# Sht3-V12P0_reg.net
KiCad netlist of a schematic drawn in Altium Designer
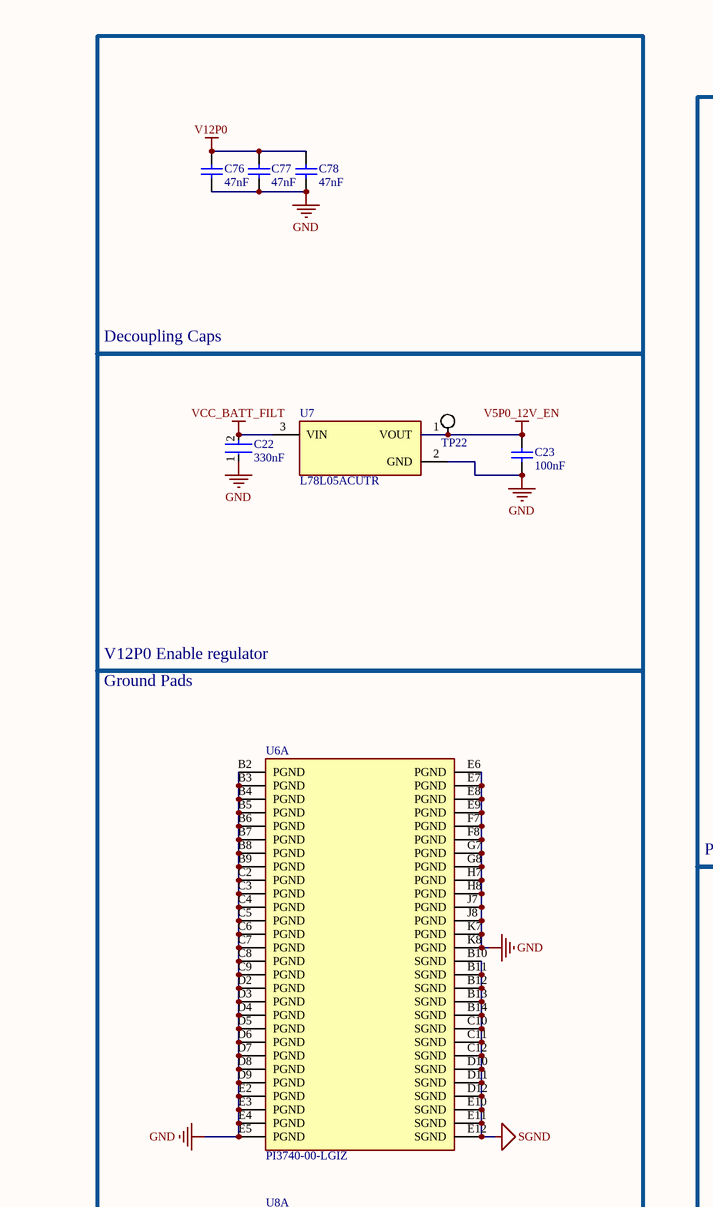
[diagram p0: Sht3-V12P0_reg.SchDoc, top left]
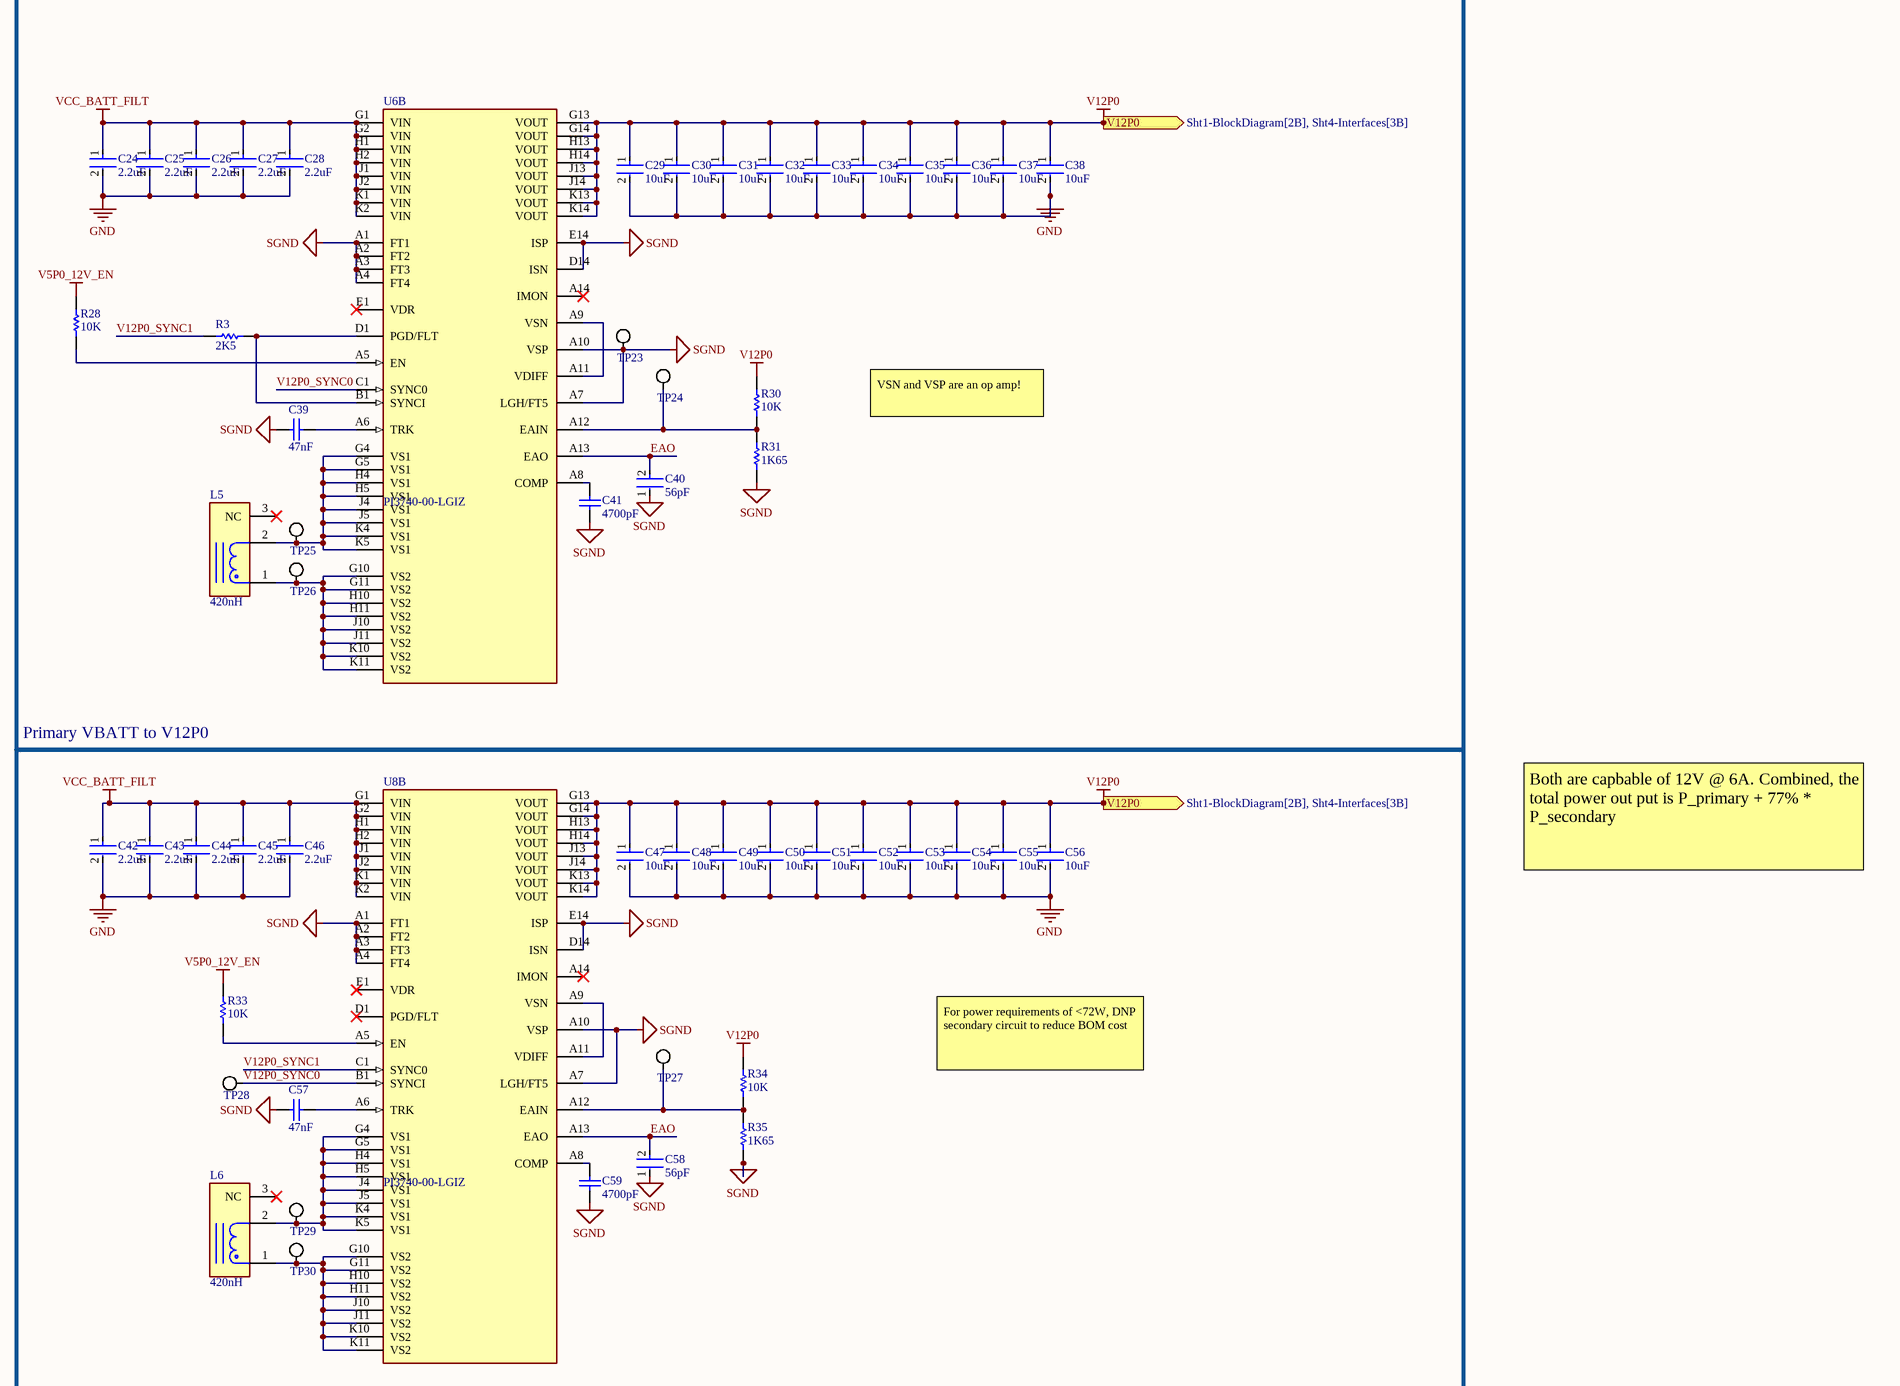
[diagram p1: Sht3-V12P0_reg.SchDoc, top right]
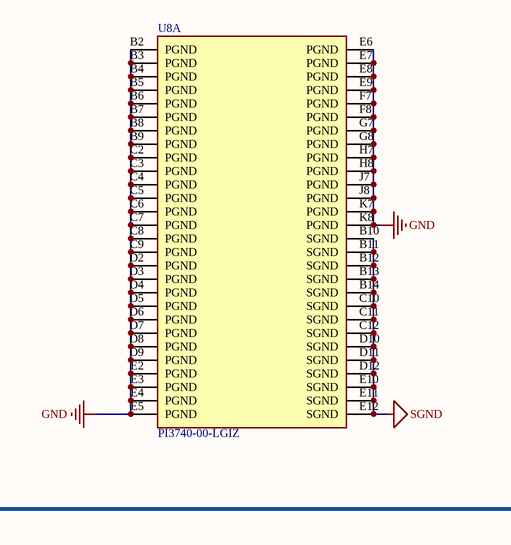
[diagram p2: Sht3-V12P0_reg.SchDoc, bottom left]
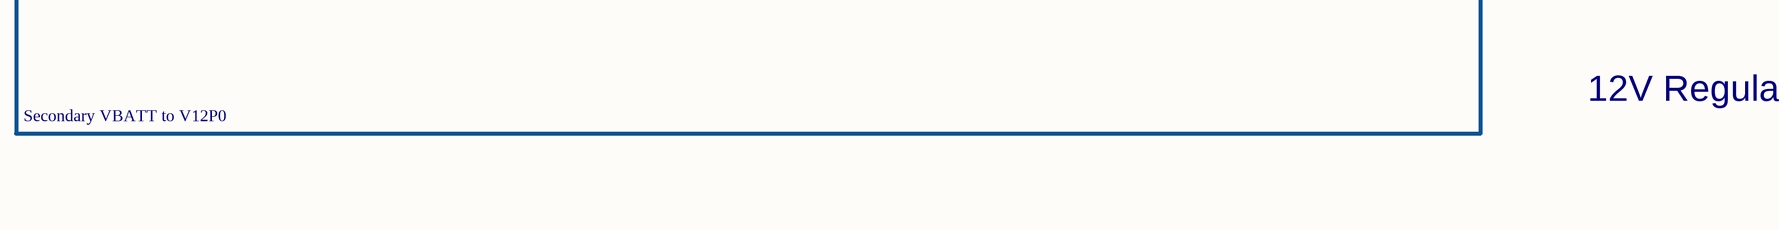
[diagram p3: Sht3-V12P0_reg.SchDoc, bottom right]

(export (version "E")
  (design (tool "Eeschema 10.0.6"))
  (components
    (comp (ref "C22")
      (value "330nF")
      (footprint "FP-C1608-080-0_1-IPC_A")
      (description "Multilayer Ceramic Capacitors 330nF ±10% 50V X7R SMD 0603")
      (fields (field (name "TOLERANCE") "10%") (field (name "VOLTAGE") "50V"))
      (libsource (lib "TAUV-Lib") (part "330nF 0603"))
    )
    (comp (ref "C23")
      (value "100nF")
      (footprint "CAPC0603(1608)100_L")
      (description "CAP 100nF 100V ±10% 0603 (1608 Metric) Thickness 1mm SMD")
      (fields (field (name "TOLERANCE") "Â±10%"))
      (libsource (lib "TAUV-Lib") (part "100nF 0603"))
    )
    (comp (ref "C24")
      (value "2.2uF")
      (footprint "FP-1210-L_3_3_0_4-W_2_5_0-IPC_B")
      (description "General Purpose Ceramic Capacitor, 1210, 2.2uF, 10%, X7R, 15%, 100V")
      (fields (field (name "TOLERANCE") "10%") (field (name "VOLTAGE") "100V"))
      (libsource (lib "TAUV-Lib") (part "2.2uF 1210"))
    )
    (comp (ref "C25")
      (value "2.2uF")
      (footprint "FP-1210-L_3_3_0_4-W_2_5_0-IPC_B")
      (description "General Purpose Ceramic Capacitor, 1210, 2.2uF, 10%, X7R, 15%, 100V")
      (fields (field (name "TOLERANCE") "10%") (field (name "VOLTAGE") "100V"))
      (libsource (lib "TAUV-Lib") (part "2.2uF 1210"))
    )
    (comp (ref "C26")
      (value "2.2uF")
      (footprint "FP-1210-L_3_3_0_4-W_2_5_0-IPC_B")
      (description "General Purpose Ceramic Capacitor, 1210, 2.2uF, 10%, X7R, 15%, 100V")
      (fields (field (name "TOLERANCE") "10%") (field (name "VOLTAGE") "100V"))
      (libsource (lib "TAUV-Lib") (part "2.2uF 1210"))
    )
    (comp (ref "C27")
      (value "2.2uF")
      (footprint "FP-1210-L_3_3_0_4-W_2_5_0-IPC_B")
      (description "General Purpose Ceramic Capacitor, 1210, 2.2uF, 10%, X7R, 15%, 100V")
      (fields (field (name "TOLERANCE") "10%") (field (name "VOLTAGE") "100V"))
      (libsource (lib "TAUV-Lib") (part "2.2uF 1210"))
    )
    (comp (ref "C28")
      (value "2.2uF")
      (footprint "FP-1210-L_3_3_0_4-W_2_5_0-IPC_B")
      (description "General Purpose Ceramic Capacitor, 1210, 2.2uF, 10%, X7R, 15%, 100V")
      (fields (field (name "TOLERANCE") "10%") (field (name "VOLTAGE") "100V"))
      (libsource (lib "TAUV-Lib") (part "2.2uF 1210"))
    )
    (comp (ref "C29")
      (value "10uF")
      (footprint "FP-GRM32-MFG")
      (description "CAP CER 10UF 50V X7R 1210")
      (fields (field (name "TOLERANCE") "10%") (field (name "MANUFACTURER PART NUMBER") "GRM32ER71H106KA12L"))
      (libsource (lib "TAUV-Lib") (part "10uF 1210"))
    )
    (comp (ref "C30")
      (value "10uF")
      (footprint "FP-GRM32-MFG")
      (description "CAP CER 10UF 50V X7R 1210")
      (fields (field (name "TOLERANCE") "10%") (field (name "MANUFACTURER PART NUMBER") "GRM32ER71H106KA12L"))
      (libsource (lib "TAUV-Lib") (part "10uF 1210"))
    )
    (comp (ref "C31")
      (value "10uF")
      (footprint "FP-GRM32-MFG")
      (description "CAP CER 10UF 50V X7R 1210")
      (fields (field (name "TOLERANCE") "10%") (field (name "MANUFACTURER PART NUMBER") "GRM32ER71H106KA12L"))
      (libsource (lib "TAUV-Lib") (part "10uF 1210"))
    )
    (comp (ref "C32")
      (value "10uF")
      (footprint "FP-GRM32-MFG")
      (description "CAP CER 10UF 50V X7R 1210")
      (fields (field (name "TOLERANCE") "10%") (field (name "MANUFACTURER PART NUMBER") "GRM32ER71H106KA12L"))
      (libsource (lib "TAUV-Lib") (part "10uF 1210"))
    )
    (comp (ref "C33")
      (value "10uF")
      (footprint "FP-GRM32-MFG")
      (description "CAP CER 10UF 50V X7R 1210")
      (fields (field (name "TOLERANCE") "10%") (field (name "MANUFACTURER PART NUMBER") "GRM32ER71H106KA12L"))
      (libsource (lib "TAUV-Lib") (part "10uF 1210"))
    )
    (comp (ref "C34")
      (value "10uF")
      (footprint "FP-GRM32-MFG")
      (description "CAP CER 10UF 50V X7R 1210")
      (fields (field (name "TOLERANCE") "10%") (field (name "MANUFACTURER PART NUMBER") "GRM32ER71H106KA12L"))
      (libsource (lib "TAUV-Lib") (part "10uF 1210"))
    )
    (comp (ref "C35")
      (value "10uF")
      (footprint "FP-GRM32-MFG")
      (description "CAP CER 10UF 50V X7R 1210")
      (fields (field (name "TOLERANCE") "10%") (field (name "MANUFACTURER PART NUMBER") "GRM32ER71H106KA12L"))
      (libsource (lib "TAUV-Lib") (part "10uF 1210"))
    )
    (comp (ref "C36")
      (value "10uF")
      (footprint "FP-GRM32-MFG")
      (description "CAP CER 10UF 50V X7R 1210")
      (fields (field (name "TOLERANCE") "10%") (field (name "MANUFACTURER PART NUMBER") "GRM32ER71H106KA12L"))
      (libsource (lib "TAUV-Lib") (part "10uF 1210"))
    )
    (comp (ref "C37")
      (value "10uF")
      (footprint "FP-GRM32-MFG")
      (description "CAP CER 10UF 50V X7R 1210")
      (fields (field (name "TOLERANCE") "10%") (field (name "MANUFACTURER PART NUMBER") "GRM32ER71H106KA12L"))
      (libsource (lib "TAUV-Lib") (part "10uF 1210"))
    )
    (comp (ref "C38")
      (value "10uF")
      (footprint "FP-GRM32-MFG")
      (description "CAP CER 10UF 50V X7R 1210")
      (fields (field (name "TOLERANCE") "10%") (field (name "MANUFACTURER PART NUMBER") "GRM32ER71H106KA12L"))
      (libsource (lib "TAUV-Lib") (part "10uF 1210"))
    )
    (comp (ref "C39")
      (value "47nF")
      (footprint "CAPC1608X90X35LL10T15")
      (description "47nF 0603")
      (fields (field (name "MANUFACTURER") "Murata") (field (name "PART NUMBER") "GRM188R71E473KA01D"))
      (libsource (lib "TAUV-Lib") (part "47nF 0603"))
    )
    (comp (ref "C40")
      (value "56pF")
      (footprint "FP-C1608-080-0_1-IPC_C")
      (description "Multilayer Ceramic Capacitors 56pF ±5% 50V C0G SMD 0603")
      (fields (field (name "TOLERANCE") "5%"))
      (libsource (lib "TAUV-Lib") (part "56pF 0603"))
    )
    (comp (ref "C41")
      (value "4700pF")
      (footprint "CAPC1608X90X35ML10T15")
      (description "4700pF 0603")
      (fields (field (name "PART NUMBER") "GRM188R72A472KA01D") (field (name "MANUFACTURER") "Murata"))
      (libsource (lib "TAUV-Lib") (part "4700pF 0603"))
    )
    (comp (ref "C42")
      (value "2.2uF")
      (footprint "FP-1210-L_3_3_0_4-W_2_5_0-IPC_B")
      (description "General Purpose Ceramic Capacitor, 1210, 2.2uF, 10%, X7R, 15%, 100V")
      (fields (field (name "TOLERANCE") "10%") (field (name "VOLTAGE") "100V"))
      (libsource (lib "TAUV-Lib") (part "2.2uF 1210"))
    )
    (comp (ref "C43")
      (value "2.2uF")
      (footprint "FP-1210-L_3_3_0_4-W_2_5_0-IPC_B")
      (description "General Purpose Ceramic Capacitor, 1210, 2.2uF, 10%, X7R, 15%, 100V")
      (fields (field (name "TOLERANCE") "10%") (field (name "VOLTAGE") "100V"))
      (libsource (lib "TAUV-Lib") (part "2.2uF 1210"))
    )
    (comp (ref "C44")
      (value "2.2uF")
      (footprint "FP-1210-L_3_3_0_4-W_2_5_0-IPC_B")
      (description "General Purpose Ceramic Capacitor, 1210, 2.2uF, 10%, X7R, 15%, 100V")
      (fields (field (name "TOLERANCE") "10%") (field (name "VOLTAGE") "100V"))
      (libsource (lib "TAUV-Lib") (part "2.2uF 1210"))
    )
    (comp (ref "C45")
      (value "2.2uF")
      (footprint "FP-1210-L_3_3_0_4-W_2_5_0-IPC_B")
      (description "General Purpose Ceramic Capacitor, 1210, 2.2uF, 10%, X7R, 15%, 100V")
      (fields (field (name "TOLERANCE") "10%") (field (name "VOLTAGE") "100V"))
      (libsource (lib "TAUV-Lib") (part "2.2uF 1210"))
    )
    (comp (ref "C46")
      (value "2.2uF")
      (footprint "FP-1210-L_3_3_0_4-W_2_5_0-IPC_B")
      (description "General Purpose Ceramic Capacitor, 1210, 2.2uF, 10%, X7R, 15%, 100V")
      (fields (field (name "TOLERANCE") "10%") (field (name "VOLTAGE") "100V"))
      (libsource (lib "TAUV-Lib") (part "2.2uF 1210"))
    )
    (comp (ref "C47")
      (value "10uF")
      (footprint "FP-GRM32-MFG")
      (description "CAP CER 10UF 50V X7R 1210")
      (fields (field (name "TOLERANCE") "10%") (field (name "MANUFACTURER PART NUMBER") "GRM32ER71H106KA12L"))
      (libsource (lib "TAUV-Lib") (part "10uF 1210"))
    )
    (comp (ref "C48")
      (value "10uF")
      (footprint "FP-GRM32-MFG")
      (description "CAP CER 10UF 50V X7R 1210")
      (fields (field (name "TOLERANCE") "10%") (field (name "MANUFACTURER PART NUMBER") "GRM32ER71H106KA12L"))
      (libsource (lib "TAUV-Lib") (part "10uF 1210"))
    )
    (comp (ref "C49")
      (value "10uF")
      (footprint "FP-GRM32-MFG")
      (description "CAP CER 10UF 50V X7R 1210")
      (fields (field (name "TOLERANCE") "10%") (field (name "MANUFACTURER PART NUMBER") "GRM32ER71H106KA12L"))
      (libsource (lib "TAUV-Lib") (part "10uF 1210"))
    )
    (comp (ref "C50")
      (value "10uF")
      (footprint "FP-GRM32-MFG")
      (description "CAP CER 10UF 50V X7R 1210")
      (fields (field (name "TOLERANCE") "10%") (field (name "MANUFACTURER PART NUMBER") "GRM32ER71H106KA12L"))
      (libsource (lib "TAUV-Lib") (part "10uF 1210"))
    )
    (comp (ref "C51")
      (value "10uF")
      (footprint "FP-GRM32-MFG")
      (description "CAP CER 10UF 50V X7R 1210")
      (fields (field (name "TOLERANCE") "10%") (field (name "MANUFACTURER PART NUMBER") "GRM32ER71H106KA12L"))
      (libsource (lib "TAUV-Lib") (part "10uF 1210"))
    )
    (comp (ref "C52")
      (value "10uF")
      (footprint "FP-GRM32-MFG")
      (description "CAP CER 10UF 50V X7R 1210")
      (fields (field (name "TOLERANCE") "10%") (field (name "MANUFACTURER PART NUMBER") "GRM32ER71H106KA12L"))
      (libsource (lib "TAUV-Lib") (part "10uF 1210"))
    )
    (comp (ref "C53")
      (value "10uF")
      (footprint "FP-GRM32-MFG")
      (description "CAP CER 10UF 50V X7R 1210")
      (fields (field (name "TOLERANCE") "10%") (field (name "MANUFACTURER PART NUMBER") "GRM32ER71H106KA12L"))
      (libsource (lib "TAUV-Lib") (part "10uF 1210"))
    )
    (comp (ref "C54")
      (value "10uF")
      (footprint "FP-GRM32-MFG")
      (description "CAP CER 10UF 50V X7R 1210")
      (fields (field (name "TOLERANCE") "10%") (field (name "MANUFACTURER PART NUMBER") "GRM32ER71H106KA12L"))
      (libsource (lib "TAUV-Lib") (part "10uF 1210"))
    )
    (comp (ref "C55")
      (value "10uF")
      (footprint "FP-GRM32-MFG")
      (description "CAP CER 10UF 50V X7R 1210")
      (fields (field (name "TOLERANCE") "10%") (field (name "MANUFACTURER PART NUMBER") "GRM32ER71H106KA12L"))
      (libsource (lib "TAUV-Lib") (part "10uF 1210"))
    )
    (comp (ref "C56")
      (value "10uF")
      (footprint "FP-GRM32-MFG")
      (description "CAP CER 10UF 50V X7R 1210")
      (fields (field (name "TOLERANCE") "10%") (field (name "MANUFACTURER PART NUMBER") "GRM32ER71H106KA12L"))
      (libsource (lib "TAUV-Lib") (part "10uF 1210"))
    )
    (comp (ref "C57")
      (value "47nF")
      (footprint "CAPC1608X90X35LL10T15")
      (description "47nF 0603")
      (fields (field (name "MANUFACTURER") "Murata") (field (name "PART NUMBER") "GRM188R71E473KA01D"))
      (libsource (lib "TAUV-Lib") (part "47nF 0603"))
    )
    (comp (ref "C58")
      (value "56pF")
      (footprint "FP-C1608-080-0_1-IPC_C")
      (description "Multilayer Ceramic Capacitors 56pF ±5% 50V C0G SMD 0603")
      (fields (field (name "TOLERANCE") "5%"))
      (libsource (lib "TAUV-Lib") (part "56pF 0603"))
    )
    (comp (ref "C59")
      (value "4700pF")
      (footprint "CAPC1608X90X35ML10T15")
      (description "4700pF 0603")
      (fields (field (name "PART NUMBER") "GRM188R72A472KA01D") (field (name "MANUFACTURER") "Murata"))
      (libsource (lib "TAUV-Lib") (part "4700pF 0603"))
    )
    (comp (ref "C76")
      (value "47nF")
      (footprint "CAPC1608X90X35LL10T15")
      (description "47nF 0603")
      (fields (field (name "MANUFACTURER") "Murata") (field (name "PART NUMBER") "GRM188R71E473KA01D"))
      (libsource (lib "TAUV-Lib") (part "47nF 0603"))
    )
    (comp (ref "C77")
      (value "47nF")
      (footprint "CAPC1608X90X35LL10T15")
      (description "47nF 0603")
      (fields (field (name "MANUFACTURER") "Murata") (field (name "PART NUMBER") "GRM188R71E473KA01D"))
      (libsource (lib "TAUV-Lib") (part "47nF 0603"))
    )
    (comp (ref "C78")
      (value "47nF")
      (footprint "CAPC1608X90X35LL10T15")
      (description "47nF 0603")
      (fields (field (name "MANUFACTURER") "Murata") (field (name "PART NUMBER") "GRM188R71E473KA01D"))
      (libsource (lib "TAUV-Lib") (part "47nF 0603"))
    )
    (comp (ref "L5")
      (value "420nH")
      (footprint "FP-HCV1206-R42-R-MFG")
      (description "HCV1206-R42-R -FIXED IND 420NH 16A 3.15 MOHM")
      (fields (field (name "TOLERANCE") "10%"))
      (libsource (lib "TAUV-Lib") (part "HCV1206-R42-R"))
    )
    (comp (ref "L6")
      (value "420nH")
      (footprint "FP-HCV1206-R42-R-MFG")
      (description "HCV1206-R42-R -FIXED IND 420NH 16A 3.15 MOHM")
      (fields (field (name "TOLERANCE") "10%"))
      (libsource (lib "TAUV-Lib") (part "HCV1206-R42-R"))
    )
    (comp (ref "R3")
      (value "2K5")
      (footprint "RESC1608X55X25NL10T15")
      (description "2.5K 0603")
      (fields (field (name "MANUFACTURER") "Yageo") (field (name "PART NUMBER") "RC0603FR-072K55L"))
      (libsource (lib "TAUV-Lib") (part "2K5 0603"))
    )
    (comp (ref "R28")
      (value "10K")
      (footprint "RESC1609X50X30NL8T20")
      (description "Chip Resistor, 10 KOhm, +/- 1%, 100 mW, -55 to 155 degC, 0603 (1608 Metric), RoHS, Tape and Reel")
      (fields (field (name "MANUFACTURER") "Vishay Semiconductor"))
      (libsource (lib "TAUV-Lib") (part "10K 0603"))
    )
    (comp (ref "R30")
      (value "10K")
      (footprint "RESC1609X50X30NL8T20")
      (description "Chip Resistor, 10 KOhm, +/- 1%, 100 mW, -55 to 155 degC, 0603 (1608 Metric), RoHS, Tape and Reel")
      (fields (field (name "MANUFACTURER") "Vishay Semiconductor"))
      (libsource (lib "TAUV-Lib") (part "10K 0603"))
    )
    (comp (ref "R31")
      (value "1K65")
      (footprint "RESC1608X55X25ML10T15")
      (description "1.65k 0603")
      (fields (field (name "PART NUMBER") "RC0603FR-071K65L") (field (name "MANUFACTURER") "Yageo"))
      (libsource (lib "TAUV-Lib") (part "1K65 0603"))
    )
    (comp (ref "R33")
      (value "10K")
      (footprint "RESC1609X50X30NL8T20")
      (description "Chip Resistor, 10 KOhm, +/- 1%, 100 mW, -55 to 155 degC, 0603 (1608 Metric), RoHS, Tape and Reel")
      (fields (field (name "MANUFACTURER") "Vishay Semiconductor"))
      (libsource (lib "TAUV-Lib") (part "10K 0603"))
    )
    (comp (ref "R34")
      (value "10K")
      (footprint "RESC1609X50X30NL8T20")
      (description "Chip Resistor, 10 KOhm, +/- 1%, 100 mW, -55 to 155 degC, 0603 (1608 Metric), RoHS, Tape and Reel")
      (fields (field (name "MANUFACTURER") "Vishay Semiconductor"))
      (libsource (lib "TAUV-Lib") (part "10K 0603"))
    )
    (comp (ref "R35")
      (value "1K65")
      (footprint "RESC1608X55X25ML10T15")
      (description "1.65k 0603")
      (fields (field (name "PART NUMBER") "RC0603FR-071K65L") (field (name "MANUFACTURER") "Yageo"))
      (libsource (lib "TAUV-Lib") (part "1K65 0603"))
    )
    (comp (ref "TP22")
      (value "~")
      (footprint "Test Point Pad")
      (description "Test point, Pad, 28 mil")
      (libsource (lib "TAUV-Lib") (part "Test Point Pad"))
    )
    (comp (ref "TP23")
      (value "~")
      (footprint "Test Point Pad")
      (description "Test point, Pad, 28 mil")
      (libsource (lib "TAUV-Lib") (part "Test Point Pad"))
    )
    (comp (ref "TP24")
      (value "~")
      (footprint "Test Point Pad")
      (description "Test point, Pad, 28 mil")
      (libsource (lib "TAUV-Lib") (part "Test Point Pad"))
    )
    (comp (ref "TP25")
      (value "~")
      (footprint "Test Point Pad")
      (description "Test point, Pad, 28 mil")
      (libsource (lib "TAUV-Lib") (part "Test Point Pad"))
    )
    (comp (ref "TP26")
      (value "~")
      (footprint "Test Point Pad")
      (description "Test point, Pad, 28 mil")
      (libsource (lib "TAUV-Lib") (part "Test Point Pad"))
    )
    (comp (ref "TP27")
      (value "~")
      (footprint "Test Point Pad")
      (description "Test point, Pad, 28 mil")
      (libsource (lib "TAUV-Lib") (part "Test Point Pad"))
    )
    (comp (ref "TP28")
      (value "~")
      (footprint "Test Point Pad")
      (description "Test point, Pad, 28 mil")
      (libsource (lib "TAUV-Lib") (part "Test Point Pad"))
    )
    (comp (ref "TP29")
      (value "~")
      (footprint "Test Point Pad")
      (description "Test point, Pad, 28 mil")
      (libsource (lib "TAUV-Lib") (part "Test Point Pad"))
    )
    (comp (ref "TP30")
      (value "~")
      (footprint "Test Point Pad")
      (description "Test point, Pad, 28 mil")
      (libsource (lib "TAUV-Lib") (part "Test Point Pad"))
    )
    (comp (ref "U6")
      (value "PI3740-00-LGIZ")
      (footprint "FP-PI3740-00-LGIZ-MFG")
      (description "DC DC CONVERTER 10-50V")
      (libsource (lib "TAUV-Lib") (part "PI3740-00-LGIZ"))
    )
    (comp (ref "U7")
      (value "L78L05ACUTR")
      (footprint "FP-SOT-89-7098166-MFG")
      (description "IC REG LINEAR 5V 100MA SOT89-3")
      (libsource (lib "TAUV-Lib") (part "L78L05ACUTR"))
    )
    (comp (ref "U8")
      (value "PI3740-00-LGIZ")
      (footprint "FP-PI3740-00-LGIZ-MFG")
      (description "DC DC CONVERTER 10-50V")
      (libsource (lib "TAUV-Lib") (part "PI3740-00-LGIZ"))
    )
  )
  (nets
    (net (code "1") (name "/EAO") (class "Default")
      (node (ref "C40") (pin "2") (pinfunction "2_2") (pintype "passive"))
      (node (ref "C58") (pin "2") (pinfunction "2_2") (pintype "passive"))
      (node (ref "U6") (pin "A13") (pinfunction "EAO_A13") (pintype "passive"))
      (node (ref "U8") (pin "A13") (pinfunction "EAO_A13") (pintype "passive"))
    )
    (net (code "2") (name "/V12P0_SYNC0") (class "Default")
      (node (ref "TP28") (pin "1") (pinfunction "1_1") (pintype "passive"))
      (node (ref "U6") (pin "C1") (pinfunction "SYNC0_C1") (pintype "input"))
      (node (ref "U8") (pin "B1") (pinfunction "SYNCI_B1") (pintype "input"))
    )
    (net (code "3") (name "/V12P0_SYNC1") (class "Default")
      (node (ref "R3") (pin "1") (pinfunction "1_1") (pintype "passive"))
      (node (ref "U8") (pin "C1") (pinfunction "SYNC0_C1") (pintype "input"))
    )
    (net (code "4") (name "GND") (class "Default")
      (node (ref "C22") (pin "1") (pinfunction "1_1") (pintype "passive"))
      (node (ref "C23") (pin "2") (pinfunction "2_2") (pintype "passive"))
      (node (ref "C24") (pin "2") (pinfunction "2_2") (pintype "passive"))
      (node (ref "C25") (pin "2") (pinfunction "2_2") (pintype "passive"))
      (node (ref "C26") (pin "2") (pinfunction "2_2") (pintype "passive"))
      (node (ref "C27") (pin "2") (pinfunction "2_2") (pintype "passive"))
      (node (ref "C28") (pin "2") (pinfunction "2_2") (pintype "passive"))
      (node (ref "C29") (pin "2") (pinfunction "2_2") (pintype "passive"))
      (node (ref "C30") (pin "2") (pinfunction "2_2") (pintype "passive"))
      (node (ref "C31") (pin "2") (pinfunction "2_2") (pintype "passive"))
      (node (ref "C32") (pin "2") (pinfunction "2_2") (pintype "passive"))
      (node (ref "C33") (pin "2") (pinfunction "2_2") (pintype "passive"))
      (node (ref "C34") (pin "2") (pinfunction "2_2") (pintype "passive"))
      (node (ref "C35") (pin "2") (pinfunction "2_2") (pintype "passive"))
      (node (ref "C36") (pin "2") (pinfunction "2_2") (pintype "passive"))
      (node (ref "C37") (pin "2") (pinfunction "2_2") (pintype "passive"))
      (node (ref "C38") (pin "2") (pinfunction "2_2") (pintype "passive"))
      (node (ref "C42") (pin "2") (pinfunction "2_2") (pintype "passive"))
      (node (ref "C43") (pin "2") (pinfunction "2_2") (pintype "passive"))
      (node (ref "C44") (pin "2") (pinfunction "2_2") (pintype "passive"))
      (node (ref "C45") (pin "2") (pinfunction "2_2") (pintype "passive"))
      (node (ref "C46") (pin "2") (pinfunction "2_2") (pintype "passive"))
      (node (ref "C47") (pin "2") (pinfunction "2_2") (pintype "passive"))
      (node (ref "C48") (pin "2") (pinfunction "2_2") (pintype "passive"))
      (node (ref "C49") (pin "2") (pinfunction "2_2") (pintype "passive"))
      (node (ref "C50") (pin "2") (pinfunction "2_2") (pintype "passive"))
      (node (ref "C51") (pin "2") (pinfunction "2_2") (pintype "passive"))
      (node (ref "C52") (pin "2") (pinfunction "2_2") (pintype "passive"))
      (node (ref "C53") (pin "2") (pinfunction "2_2") (pintype "passive"))
      (node (ref "C54") (pin "2") (pinfunction "2_2") (pintype "passive"))
      (node (ref "C55") (pin "2") (pinfunction "2_2") (pintype "passive"))
      (node (ref "C56") (pin "2") (pinfunction "2_2") (pintype "passive"))
      (node (ref "C76") (pin "2") (pinfunction "2_2") (pintype "passive"))
      (node (ref "C77") (pin "2") (pinfunction "2_2") (pintype "passive"))
      (node (ref "C78") (pin "2") (pinfunction "2_2") (pintype "passive"))
      (node (ref "U6") (pin "B2") (pinfunction "PGND_B2") (pintype "power_in"))
      (node (ref "U6") (pin "B3") (pinfunction "PGND_B3") (pintype "power_in"))
      (node (ref "U6") (pin "B4") (pinfunction "PGND_B4") (pintype "power_in"))
      (node (ref "U6") (pin "B5") (pinfunction "PGND_B5") (pintype "power_in"))
      (node (ref "U6") (pin "B6") (pinfunction "PGND_B6") (pintype "power_in"))
      (node (ref "U6") (pin "B7") (pinfunction "PGND_B7") (pintype "power_in"))
      (node (ref "U6") (pin "B8") (pinfunction "PGND_B8") (pintype "power_in"))
      (node (ref "U6") (pin "B9") (pinfunction "PGND_B9") (pintype "power_in"))
      (node (ref "U6") (pin "C2") (pinfunction "PGND_C2") (pintype "power_in"))
      (node (ref "U6") (pin "C3") (pinfunction "PGND_C3") (pintype "power_in"))
      (node (ref "U6") (pin "C4") (pinfunction "PGND_C4") (pintype "power_in"))
      (node (ref "U6") (pin "C5") (pinfunction "PGND_C5") (pintype "power_in"))
      (node (ref "U6") (pin "C6") (pinfunction "PGND_C6") (pintype "power_in"))
      (node (ref "U6") (pin "C7") (pinfunction "PGND_C7") (pintype "power_in"))
      (node (ref "U6") (pin "C8") (pinfunction "PGND_C8") (pintype "power_in"))
      (node (ref "U6") (pin "C9") (pinfunction "PGND_C9") (pintype "power_in"))
      (node (ref "U6") (pin "D2") (pinfunction "PGND_D2") (pintype "power_in"))
      (node (ref "U6") (pin "D3") (pinfunction "PGND_D3") (pintype "power_in"))
      (node (ref "U6") (pin "D4") (pinfunction "PGND_D4") (pintype "power_in"))
      (node (ref "U6") (pin "D5") (pinfunction "PGND_D5") (pintype "power_in"))
      (node (ref "U6") (pin "D6") (pinfunction "PGND_D6") (pintype "power_in"))
      (node (ref "U6") (pin "D7") (pinfunction "PGND_D7") (pintype "power_in"))
      (node (ref "U6") (pin "D8") (pinfunction "PGND_D8") (pintype "power_in"))
      (node (ref "U6") (pin "D9") (pinfunction "PGND_D9") (pintype "power_in"))
      (node (ref "U6") (pin "E2") (pinfunction "PGND_E2") (pintype "power_in"))
      (node (ref "U6") (pin "E3") (pinfunction "PGND_E3") (pintype "power_in"))
      (node (ref "U6") (pin "E4") (pinfunction "PGND_E4") (pintype "power_in"))
      (node (ref "U6") (pin "E5") (pinfunction "PGND_E5") (pintype "power_in"))
      (node (ref "U6") (pin "E6") (pinfunction "PGND_E6") (pintype "power_in"))
      (node (ref "U6") (pin "E7") (pinfunction "PGND_E7") (pintype "power_in"))
      (node (ref "U6") (pin "E8") (pinfunction "PGND_E8") (pintype "power_in"))
      (node (ref "U6") (pin "E9") (pinfunction "PGND_E9") (pintype "power_in"))
      (node (ref "U6") (pin "F7") (pinfunction "PGND_F7") (pintype "power_in"))
      (node (ref "U6") (pin "F8") (pinfunction "PGND_F8") (pintype "power_in"))
      (node (ref "U6") (pin "G7") (pinfunction "PGND_G7") (pintype "power_in"))
      (node (ref "U6") (pin "G8") (pinfunction "PGND_G8") (pintype "power_in"))
      (node (ref "U6") (pin "H7") (pinfunction "PGND_H7") (pintype "power_in"))
      (node (ref "U6") (pin "H8") (pinfunction "PGND_H8") (pintype "power_in"))
      (node (ref "U6") (pin "J7") (pinfunction "PGND_J7") (pintype "power_in"))
      (node (ref "U6") (pin "J8") (pinfunction "PGND_J8") (pintype "power_in"))
      (node (ref "U6") (pin "K7") (pinfunction "PGND_K7") (pintype "power_in"))
      (node (ref "U6") (pin "K8") (pinfunction "PGND_K8") (pintype "power_in"))
      (node (ref "U7") (pin "2") (pinfunction "GND_2") (pintype "power_in"))
      (node (ref "U8") (pin "B2") (pinfunction "PGND_B2") (pintype "power_in"))
      (node (ref "U8") (pin "B3") (pinfunction "PGND_B3") (pintype "power_in"))
      (node (ref "U8") (pin "B4") (pinfunction "PGND_B4") (pintype "power_in"))
      (node (ref "U8") (pin "B5") (pinfunction "PGND_B5") (pintype "power_in"))
      (node (ref "U8") (pin "B6") (pinfunction "PGND_B6") (pintype "power_in"))
      (node (ref "U8") (pin "B7") (pinfunction "PGND_B7") (pintype "power_in"))
      (node (ref "U8") (pin "B8") (pinfunction "PGND_B8") (pintype "power_in"))
      (node (ref "U8") (pin "B9") (pinfunction "PGND_B9") (pintype "power_in"))
      (node (ref "U8") (pin "C2") (pinfunction "PGND_C2") (pintype "power_in"))
      (node (ref "U8") (pin "C3") (pinfunction "PGND_C3") (pintype "power_in"))
      (node (ref "U8") (pin "C4") (pinfunction "PGND_C4") (pintype "power_in"))
      (node (ref "U8") (pin "C5") (pinfunction "PGND_C5") (pintype "power_in"))
      (node (ref "U8") (pin "C6") (pinfunction "PGND_C6") (pintype "power_in"))
      (node (ref "U8") (pin "C7") (pinfunction "PGND_C7") (pintype "power_in"))
      (node (ref "U8") (pin "C8") (pinfunction "PGND_C8") (pintype "power_in"))
      (node (ref "U8") (pin "C9") (pinfunction "PGND_C9") (pintype "power_in"))
      (node (ref "U8") (pin "D2") (pinfunction "PGND_D2") (pintype "power_in"))
      (node (ref "U8") (pin "D3") (pinfunction "PGND_D3") (pintype "power_in"))
      (node (ref "U8") (pin "D4") (pinfunction "PGND_D4") (pintype "power_in"))
      (node (ref "U8") (pin "D5") (pinfunction "PGND_D5") (pintype "power_in"))
      (node (ref "U8") (pin "D6") (pinfunction "PGND_D6") (pintype "power_in"))
      (node (ref "U8") (pin "D7") (pinfunction "PGND_D7") (pintype "power_in"))
      (node (ref "U8") (pin "D8") (pinfunction "PGND_D8") (pintype "power_in"))
      (node (ref "U8") (pin "D9") (pinfunction "PGND_D9") (pintype "power_in"))
      (node (ref "U8") (pin "E2") (pinfunction "PGND_E2") (pintype "power_in"))
      (node (ref "U8") (pin "E3") (pinfunction "PGND_E3") (pintype "power_in"))
      (node (ref "U8") (pin "E4") (pinfunction "PGND_E4") (pintype "power_in"))
      (node (ref "U8") (pin "E5") (pinfunction "PGND_E5") (pintype "power_in"))
      (node (ref "U8") (pin "E6") (pinfunction "PGND_E6") (pintype "power_in"))
      (node (ref "U8") (pin "E7") (pinfunction "PGND_E7") (pintype "power_in"))
      (node (ref "U8") (pin "E8") (pinfunction "PGND_E8") (pintype "power_in"))
      (node (ref "U8") (pin "E9") (pinfunction "PGND_E9") (pintype "power_in"))
      (node (ref "U8") (pin "F7") (pinfunction "PGND_F7") (pintype "power_in"))
      (node (ref "U8") (pin "F8") (pinfunction "PGND_F8") (pintype "power_in"))
      (node (ref "U8") (pin "G7") (pinfunction "PGND_G7") (pintype "power_in"))
      (node (ref "U8") (pin "G8") (pinfunction "PGND_G8") (pintype "power_in"))
      (node (ref "U8") (pin "H7") (pinfunction "PGND_H7") (pintype "power_in"))
      (node (ref "U8") (pin "H8") (pinfunction "PGND_H8") (pintype "power_in"))
      (node (ref "U8") (pin "J7") (pinfunction "PGND_J7") (pintype "power_in"))
      (node (ref "U8") (pin "J8") (pinfunction "PGND_J8") (pintype "power_in"))
      (node (ref "U8") (pin "K7") (pinfunction "PGND_K7") (pintype "power_in"))
      (node (ref "U8") (pin "K8") (pinfunction "PGND_K8") (pintype "power_in"))
    )
    (net (code "5") (name "Net-(L5-Pad1)") (class "Default")
      (node (ref "L5") (pin "1") (pinfunction "1_1") (pintype "passive"))
      (node (ref "TP26") (pin "1") (pinfunction "1_1") (pintype "passive"))
      (node (ref "U6") (pin "G10") (pinfunction "VS2_G10") (pintype "passive"))
      (node (ref "U6") (pin "G11") (pinfunction "VS2_G11") (pintype "passive"))
      (node (ref "U6") (pin "H10") (pinfunction "VS2_H10") (pintype "passive"))
      (node (ref "U6") (pin "H11") (pinfunction "VS2_H11") (pintype "passive"))
      (node (ref "U6") (pin "J10") (pinfunction "VS2_J10") (pintype "passive"))
      (node (ref "U6") (pin "J11") (pinfunction "VS2_J11") (pintype "passive"))
      (node (ref "U6") (pin "K10") (pinfunction "VS2_K10") (pintype "passive"))
      (node (ref "U6") (pin "K11") (pinfunction "VS2_K11") (pintype "passive"))
    )
    (net (code "6") (name "Net-(L5-Pad2)") (class "Default")
      (node (ref "L5") (pin "2") (pinfunction "2_2") (pintype "passive"))
      (node (ref "TP25") (pin "1") (pinfunction "1_1") (pintype "passive"))
      (node (ref "U6") (pin "G4") (pinfunction "VS1_G4") (pintype "passive"))
      (node (ref "U6") (pin "G5") (pinfunction "VS1_G5") (pintype "passive"))
      (node (ref "U6") (pin "H4") (pinfunction "VS1_H4") (pintype "passive"))
      (node (ref "U6") (pin "H5") (pinfunction "VS1_H5") (pintype "passive"))
      (node (ref "U6") (pin "J4") (pinfunction "VS1_J4") (pintype "passive"))
      (node (ref "U6") (pin "J5") (pinfunction "VS1_J5") (pintype "passive"))
      (node (ref "U6") (pin "K4") (pinfunction "VS1_K4") (pintype "passive"))
      (node (ref "U6") (pin "K5") (pinfunction "VS1_K5") (pintype "passive"))
    )
    (net (code "7") (name "Net-(L6-Pad1)") (class "Default")
      (node (ref "L6") (pin "1") (pinfunction "1_1") (pintype "passive"))
      (node (ref "TP30") (pin "1") (pinfunction "1_1") (pintype "passive"))
      (node (ref "U8") (pin "G10") (pinfunction "VS2_G10") (pintype "passive"))
      (node (ref "U8") (pin "G11") (pinfunction "VS2_G11") (pintype "passive"))
      (node (ref "U8") (pin "H10") (pinfunction "VS2_H10") (pintype "passive"))
      (node (ref "U8") (pin "H11") (pinfunction "VS2_H11") (pintype "passive"))
      (node (ref "U8") (pin "J10") (pinfunction "VS2_J10") (pintype "passive"))
      (node (ref "U8") (pin "J11") (pinfunction "VS2_J11") (pintype "passive"))
      (node (ref "U8") (pin "K10") (pinfunction "VS2_K10") (pintype "passive"))
      (node (ref "U8") (pin "K11") (pinfunction "VS2_K11") (pintype "passive"))
    )
    (net (code "8") (name "Net-(L6-Pad2)") (class "Default")
      (node (ref "L6") (pin "2") (pinfunction "2_2") (pintype "passive"))
      (node (ref "TP29") (pin "1") (pinfunction "1_1") (pintype "passive"))
      (node (ref "U8") (pin "G4") (pinfunction "VS1_G4") (pintype "passive"))
      (node (ref "U8") (pin "G5") (pinfunction "VS1_G5") (pintype "passive"))
      (node (ref "U8") (pin "H4") (pinfunction "VS1_H4") (pintype "passive"))
      (node (ref "U8") (pin "H5") (pinfunction "VS1_H5") (pintype "passive"))
      (node (ref "U8") (pin "J4") (pinfunction "VS1_J4") (pintype "passive"))
      (node (ref "U8") (pin "J5") (pinfunction "VS1_J5") (pintype "passive"))
      (node (ref "U8") (pin "K4") (pinfunction "VS1_K4") (pintype "passive"))
      (node (ref "U8") (pin "K5") (pinfunction "VS1_K5") (pintype "passive"))
    )
    (net (code "9") (name "Net-(U6B-COMP)") (class "Default")
      (node (ref "C41") (pin "1") (pinfunction "1_1") (pintype "passive"))
      (node (ref "U6") (pin "A8") (pinfunction "COMP_A8") (pintype "passive"))
    )
    (net (code "10") (name "Net-(U6B-EAIN)") (class "Default")
      (node (ref "R30") (pin "1") (pinfunction "1_1") (pintype "passive"))
      (node (ref "R31") (pin "2") (pinfunction "2_2") (pintype "passive"))
      (node (ref "TP24") (pin "1") (pinfunction "1_1") (pintype "passive"))
      (node (ref "U6") (pin "A12") (pinfunction "EAIN_A12") (pintype "tri_state"))
    )
    (net (code "11") (name "Net-(U6B-EN)") (class "Default")
      (node (ref "R28") (pin "1") (pinfunction "1_1") (pintype "passive"))
      (node (ref "U6") (pin "A5") (pinfunction "EN_A5") (pintype "input"))
    )
    (net (code "12") (name "Net-(U6B-PGD{slash}FLT)") (class "Default")
      (node (ref "R3") (pin "2") (pinfunction "2_2") (pintype "passive"))
      (node (ref "U6") (pin "B1") (pinfunction "SYNCI_B1") (pintype "input"))
      (node (ref "U6") (pin "D1") (pinfunction "PGD/FLT_D1") (pintype "power_in"))
    )
    (net (code "13") (name "Net-(U6B-TRK)") (class "Default")
      (node (ref "C39") (pin "1") (pinfunction "1_1") (pintype "passive"))
      (node (ref "U6") (pin "A6") (pinfunction "TRK_A6") (pintype "input"))
    )
    (net (code "14") (name "Net-(U6B-VDIFF)") (class "Default")
      (node (ref "U6") (pin "A11") (pinfunction "VDIFF_A11") (pintype "passive"))
      (node (ref "U6") (pin "A9") (pinfunction "VSN_A9") (pintype "tri_state"))
    )
    (net (code "15") (name "Net-(U8B-COMP)") (class "Default")
      (node (ref "C59") (pin "1") (pinfunction "1_1") (pintype "passive"))
      (node (ref "U8") (pin "A8") (pinfunction "COMP_A8") (pintype "passive"))
    )
    (net (code "16") (name "Net-(U8B-EAIN)") (class "Default")
      (node (ref "R34") (pin "1") (pinfunction "1_1") (pintype "passive"))
      (node (ref "R35") (pin "2") (pinfunction "2_2") (pintype "passive"))
      (node (ref "TP27") (pin "1") (pinfunction "1_1") (pintype "passive"))
      (node (ref "U8") (pin "A12") (pinfunction "EAIN_A12") (pintype "tri_state"))
    )
    (net (code "17") (name "Net-(U8B-EN)") (class "Default")
      (node (ref "R33") (pin "1") (pinfunction "1_1") (pintype "passive"))
      (node (ref "U8") (pin "A5") (pinfunction "EN_A5") (pintype "input"))
    )
    (net (code "18") (name "Net-(U8B-TRK)") (class "Default")
      (node (ref "C57") (pin "2") (pinfunction "2_2") (pintype "passive"))
      (node (ref "U8") (pin "A6") (pinfunction "TRK_A6") (pintype "input"))
    )
    (net (code "19") (name "Net-(U8B-VDIFF)") (class "Default")
      (node (ref "U8") (pin "A11") (pinfunction "VDIFF_A11") (pintype "passive"))
      (node (ref "U8") (pin "A9") (pinfunction "VSN_A9") (pintype "tri_state"))
    )
    (net (code "20") (name "SGND") (class "Default")
      (node (ref "C39") (pin "2") (pinfunction "2_2") (pintype "passive"))
      (node (ref "C40") (pin "1") (pinfunction "1_1") (pintype "passive"))
      (node (ref "C41") (pin "2") (pinfunction "2_2") (pintype "passive"))
      (node (ref "C57") (pin "1") (pinfunction "1_1") (pintype "passive"))
      (node (ref "C58") (pin "1") (pinfunction "1_1") (pintype "passive"))
      (node (ref "C59") (pin "2") (pinfunction "2_2") (pintype "passive"))
      (node (ref "R31") (pin "1") (pinfunction "1_1") (pintype "passive"))
      (node (ref "R35") (pin "1") (pinfunction "1_1") (pintype "passive"))
      (node (ref "TP23") (pin "1") (pinfunction "1_1") (pintype "passive"))
      (node (ref "U6") (pin "A1") (pinfunction "FT1_A1") (pintype "passive"))
      (node (ref "U6") (pin "A10") (pinfunction "VSP_A10") (pintype "tri_state"))
      (node (ref "U6") (pin "A2") (pinfunction "FT2_A2") (pintype "passive"))
      (node (ref "U6") (pin "A3") (pinfunction "FT3_A3") (pintype "passive"))
      (node (ref "U6") (pin "A4") (pinfunction "FT4_A4") (pintype "passive"))
      (node (ref "U6") (pin "A7") (pinfunction "LGH/FT5_A7") (pintype "passive"))
      (node (ref "U6") (pin "B10") (pinfunction "SGND_B10") (pintype "power_in"))
      (node (ref "U6") (pin "B11") (pinfunction "SGND_B11") (pintype "power_in"))
      (node (ref "U6") (pin "B12") (pinfunction "SGND_B12") (pintype "power_in"))
      (node (ref "U6") (pin "B13") (pinfunction "SGND_B13") (pintype "power_in"))
      (node (ref "U6") (pin "B14") (pinfunction "SGND_B14") (pintype "power_in"))
      (node (ref "U6") (pin "C10") (pinfunction "SGND_C10") (pintype "power_in"))
      (node (ref "U6") (pin "C11") (pinfunction "SGND_C11") (pintype "power_in"))
      (node (ref "U6") (pin "C12") (pinfunction "SGND_C12") (pintype "power_in"))
      (node (ref "U6") (pin "D10") (pinfunction "SGND_D10") (pintype "power_in"))
      (node (ref "U6") (pin "D11") (pinfunction "SGND_D11") (pintype "power_in"))
      (node (ref "U6") (pin "D12") (pinfunction "SGND_D12") (pintype "power_in"))
      (node (ref "U6") (pin "D14") (pinfunction "ISN_D14") (pintype "tri_state"))
      (node (ref "U6") (pin "E10") (pinfunction "SGND_E10") (pintype "power_in"))
      (node (ref "U6") (pin "E11") (pinfunction "SGND_E11") (pintype "power_in"))
      (node (ref "U6") (pin "E12") (pinfunction "SGND_E12") (pintype "power_in"))
      (node (ref "U6") (pin "E14") (pinfunction "ISP_E14") (pintype "tri_state"))
      (node (ref "U8") (pin "A1") (pinfunction "FT1_A1") (pintype "passive"))
      (node (ref "U8") (pin "A10") (pinfunction "VSP_A10") (pintype "tri_state"))
      (node (ref "U8") (pin "A2") (pinfunction "FT2_A2") (pintype "passive"))
      (node (ref "U8") (pin "A3") (pinfunction "FT3_A3") (pintype "passive"))
      (node (ref "U8") (pin "A4") (pinfunction "FT4_A4") (pintype "passive"))
      (node (ref "U8") (pin "A7") (pinfunction "LGH/FT5_A7") (pintype "passive"))
      (node (ref "U8") (pin "B10") (pinfunction "SGND_B10") (pintype "power_in"))
      (node (ref "U8") (pin "B11") (pinfunction "SGND_B11") (pintype "power_in"))
      (node (ref "U8") (pin "B12") (pinfunction "SGND_B12") (pintype "power_in"))
      (node (ref "U8") (pin "B13") (pinfunction "SGND_B13") (pintype "power_in"))
      (node (ref "U8") (pin "B14") (pinfunction "SGND_B14") (pintype "power_in"))
      (node (ref "U8") (pin "C10") (pinfunction "SGND_C10") (pintype "power_in"))
      (node (ref "U8") (pin "C11") (pinfunction "SGND_C11") (pintype "power_in"))
      (node (ref "U8") (pin "C12") (pinfunction "SGND_C12") (pintype "power_in"))
      (node (ref "U8") (pin "D10") (pinfunction "SGND_D10") (pintype "power_in"))
      (node (ref "U8") (pin "D11") (pinfunction "SGND_D11") (pintype "power_in"))
      (node (ref "U8") (pin "D12") (pinfunction "SGND_D12") (pintype "power_in"))
      (node (ref "U8") (pin "D14") (pinfunction "ISN_D14") (pintype "tri_state"))
      (node (ref "U8") (pin "E10") (pinfunction "SGND_E10") (pintype "power_in"))
      (node (ref "U8") (pin "E11") (pinfunction "SGND_E11") (pintype "power_in"))
      (node (ref "U8") (pin "E12") (pinfunction "SGND_E12") (pintype "power_in"))
      (node (ref "U8") (pin "E14") (pinfunction "ISP_E14") (pintype "tri_state"))
    )
    (net (code "21") (name "V5P0_12V_EN") (class "Default")
      (node (ref "C23") (pin "1") (pinfunction "1_1") (pintype "passive"))
      (node (ref "R28") (pin "2") (pinfunction "2_2") (pintype "passive"))
      (node (ref "R33") (pin "2") (pinfunction "2_2") (pintype "passive"))
      (node (ref "TP22") (pin "1") (pinfunction "1_1") (pintype "passive"))
      (node (ref "U7") (pin "1") (pinfunction "VOUT_1") (pintype "power_in"))
    )
    (net (code "22") (name "V12P0") (class "Default")
      (node (ref "C29") (pin "1") (pinfunction "1_1") (pintype "passive"))
      (node (ref "C30") (pin "1") (pinfunction "1_1") (pintype "passive"))
      (node (ref "C31") (pin "1") (pinfunction "1_1") (pintype "passive"))
      (node (ref "C32") (pin "1") (pinfunction "1_1") (pintype "passive"))
      (node (ref "C33") (pin "1") (pinfunction "1_1") (pintype "passive"))
      (node (ref "C34") (pin "1") (pinfunction "1_1") (pintype "passive"))
      (node (ref "C35") (pin "1") (pinfunction "1_1") (pintype "passive"))
      (node (ref "C36") (pin "1") (pinfunction "1_1") (pintype "passive"))
      (node (ref "C37") (pin "1") (pinfunction "1_1") (pintype "passive"))
      (node (ref "C38") (pin "1") (pinfunction "1_1") (pintype "passive"))
      (node (ref "C47") (pin "1") (pinfunction "1_1") (pintype "passive"))
      (node (ref "C48") (pin "1") (pinfunction "1_1") (pintype "passive"))
      (node (ref "C49") (pin "1") (pinfunction "1_1") (pintype "passive"))
      (node (ref "C50") (pin "1") (pinfunction "1_1") (pintype "passive"))
      (node (ref "C51") (pin "1") (pinfunction "1_1") (pintype "passive"))
      (node (ref "C52") (pin "1") (pinfunction "1_1") (pintype "passive"))
      (node (ref "C53") (pin "1") (pinfunction "1_1") (pintype "passive"))
      (node (ref "C54") (pin "1") (pinfunction "1_1") (pintype "passive"))
      (node (ref "C55") (pin "1") (pinfunction "1_1") (pintype "passive"))
      (node (ref "C56") (pin "1") (pinfunction "1_1") (pintype "passive"))
      (node (ref "C76") (pin "1") (pinfunction "1_1") (pintype "passive"))
      (node (ref "C77") (pin "1") (pinfunction "1_1") (pintype "passive"))
      (node (ref "C78") (pin "1") (pinfunction "1_1") (pintype "passive"))
      (node (ref "R30") (pin "2") (pinfunction "2_2") (pintype "passive"))
      (node (ref "R34") (pin "2") (pinfunction "2_2") (pintype "passive"))
      (node (ref "U6") (pin "G13") (pinfunction "VOUT_G13") (pintype "power_in"))
      (node (ref "U6") (pin "G14") (pinfunction "VOUT_G14") (pintype "power_in"))
      (node (ref "U6") (pin "H13") (pinfunction "VOUT_H13") (pintype "power_in"))
      (node (ref "U6") (pin "H14") (pinfunction "VOUT_H14") (pintype "power_in"))
      (node (ref "U6") (pin "J13") (pinfunction "VOUT_J13") (pintype "power_in"))
      (node (ref "U6") (pin "J14") (pinfunction "VOUT_J14") (pintype "power_in"))
      (node (ref "U6") (pin "K13") (pinfunction "VOUT_K13") (pintype "power_in"))
      (node (ref "U6") (pin "K14") (pinfunction "VOUT_K14") (pintype "power_in"))
      (node (ref "U8") (pin "G13") (pinfunction "VOUT_G13") (pintype "power_in"))
      (node (ref "U8") (pin "G14") (pinfunction "VOUT_G14") (pintype "power_in"))
      (node (ref "U8") (pin "H13") (pinfunction "VOUT_H13") (pintype "power_in"))
      (node (ref "U8") (pin "H14") (pinfunction "VOUT_H14") (pintype "power_in"))
      (node (ref "U8") (pin "J13") (pinfunction "VOUT_J13") (pintype "power_in"))
      (node (ref "U8") (pin "J14") (pinfunction "VOUT_J14") (pintype "power_in"))
      (node (ref "U8") (pin "K13") (pinfunction "VOUT_K13") (pintype "power_in"))
      (node (ref "U8") (pin "K14") (pinfunction "VOUT_K14") (pintype "power_in"))
    )
    (net (code "23") (name "VCC_BATT_FILT") (class "Default")
      (node (ref "C22") (pin "2") (pinfunction "2_2") (pintype "passive"))
      (node (ref "C24") (pin "1") (pinfunction "1_1") (pintype "passive"))
      (node (ref "C25") (pin "1") (pinfunction "1_1") (pintype "passive"))
      (node (ref "C26") (pin "1") (pinfunction "1_1") (pintype "passive"))
      (node (ref "C27") (pin "1") (pinfunction "1_1") (pintype "passive"))
      (node (ref "C28") (pin "1") (pinfunction "1_1") (pintype "passive"))
      (node (ref "C42") (pin "1") (pinfunction "1_1") (pintype "passive"))
      (node (ref "C43") (pin "1") (pinfunction "1_1") (pintype "passive"))
      (node (ref "C44") (pin "1") (pinfunction "1_1") (pintype "passive"))
      (node (ref "C45") (pin "1") (pinfunction "1_1") (pintype "passive"))
      (node (ref "C46") (pin "1") (pinfunction "1_1") (pintype "passive"))
      (node (ref "U6") (pin "G1") (pinfunction "VIN_G1") (pintype "power_in"))
      (node (ref "U6") (pin "G2") (pinfunction "VIN_G2") (pintype "power_in"))
      (node (ref "U6") (pin "H1") (pinfunction "VIN_H1") (pintype "power_in"))
      (node (ref "U6") (pin "H2") (pinfunction "VIN_H2") (pintype "power_in"))
      (node (ref "U6") (pin "J1") (pinfunction "VIN_J1") (pintype "power_in"))
      (node (ref "U6") (pin "J2") (pinfunction "VIN_J2") (pintype "power_in"))
      (node (ref "U6") (pin "K1") (pinfunction "VIN_K1") (pintype "power_in"))
      (node (ref "U6") (pin "K2") (pinfunction "VIN_K2") (pintype "power_in"))
      (node (ref "U7") (pin "3") (pinfunction "VIN_3") (pintype "power_in"))
      (node (ref "U8") (pin "G1") (pinfunction "VIN_G1") (pintype "power_in"))
      (node (ref "U8") (pin "G2") (pinfunction "VIN_G2") (pintype "power_in"))
      (node (ref "U8") (pin "H1") (pinfunction "VIN_H1") (pintype "power_in"))
      (node (ref "U8") (pin "H2") (pinfunction "VIN_H2") (pintype "power_in"))
      (node (ref "U8") (pin "J1") (pinfunction "VIN_J1") (pintype "power_in"))
      (node (ref "U8") (pin "J2") (pinfunction "VIN_J2") (pintype "power_in"))
      (node (ref "U8") (pin "K1") (pinfunction "VIN_K1") (pintype "power_in"))
      (node (ref "U8") (pin "K2") (pinfunction "VIN_K2") (pintype "power_in"))
    )
    (net (code "24") (name "unconnected-(L5-NC-Pad3)") (class "Default")
      (node (ref "L5") (pin "3") (pinfunction "NC_3") (pintype "passive+no_connect"))
    )
    (net (code "25") (name "unconnected-(L6-NC-Pad3)") (class "Default")
      (node (ref "L6") (pin "3") (pinfunction "NC_3") (pintype "passive+no_connect"))
    )
    (net (code "26") (name "unconnected-(U6B-IMON-PadA14)") (class "Default")
      (node (ref "U6") (pin "A14") (pinfunction "IMON_A14") (pintype "passive+no_connect"))
    )
    (net (code "27") (name "unconnected-(U6B-VDR-PadE1)") (class "Default")
      (node (ref "U6") (pin "E1") (pinfunction "VDR_E1") (pintype "power_in+no_connect"))
    )
    (net (code "28") (name "unconnected-(U8B-IMON-PadA14)") (class "Default")
      (node (ref "U8") (pin "A14") (pinfunction "IMON_A14") (pintype "passive+no_connect"))
    )
    (net (code "29") (name "unconnected-(U8B-PGD{slash}FLT-PadD1)") (class "Default")
      (node (ref "U8") (pin "D1") (pinfunction "PGD/FLT_D1") (pintype "power_in+no_connect"))
    )
    (net (code "30") (name "unconnected-(U8B-VDR-PadE1)") (class "Default")
      (node (ref "U8") (pin "E1") (pinfunction "VDR_E1") (pintype "power_in+no_connect"))
    )
  )
)
